# aufsatz_v2_3_usb.net
KiCad netlist of a schematic drawn in EAGLE
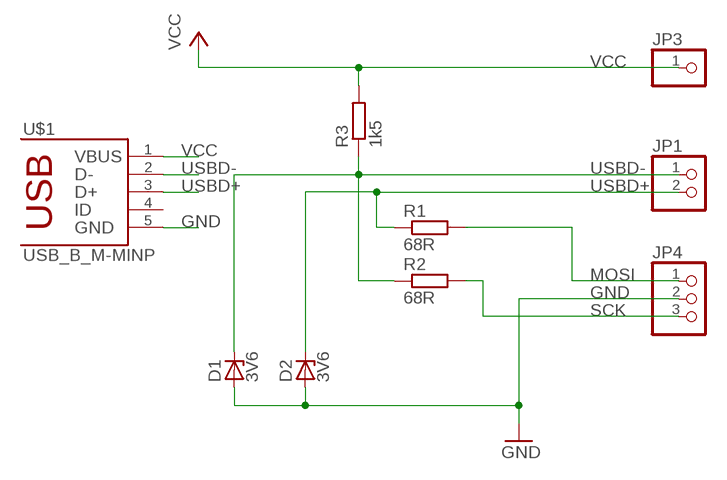
[diagram p0: schematic, sheet 1]

(export (version "E")
  (design (tool "Eeschema 10.0.6"))
  (components
    (comp (ref "D1")
      (value "3V6")
      (footprint "eagle-import:SOD80C")
      (libsource (lib "eagle-import") (part "ZENER-DIODESOD80C"))
    )
    (comp (ref "D2")
      (value "3V6")
      (footprint "eagle-import:SOD80C")
      (libsource (lib "eagle-import") (part "ZENER-DIODESOD80C"))
    )
    (comp (ref "JP1")
      (value "PINHD-1X2")
      (footprint "eagle-import:1X02")
      (libsource (lib "eagle-import") (part "PINHD-1X2"))
    )
    (comp (ref "JP3")
      (value "PINHD-1X1")
      (footprint "eagle-import:1X01")
      (libsource (lib "eagle-import") (part "PINHD-1X1"))
    )
    (comp (ref "JP4")
      (value "PINHD-1X3")
      (footprint "eagle-import:1X03")
      (libsource (lib "eagle-import") (part "PINHD-1X3"))
    )
    (comp (ref "R1")
      (value "68R")
      (footprint "eagle-import:R0805")
      (libsource (lib "eagle-import") (part "R-EU_R0805"))
    )
    (comp (ref "R2")
      (value "68R")
      (footprint "eagle-import:R0805")
      (libsource (lib "eagle-import") (part "R-EU_R0805"))
    )
    (comp (ref "R3")
      (value "1k5")
      (footprint "eagle-import:R0805")
      (libsource (lib "eagle-import") (part "R-EU_R0805"))
    )
    (comp (ref "U$1")
      (value "USB_B_M-MINP")
      (footprint "eagle-import:USB_B_MINI-PRINT")
      (libsource (lib "eagle-import") (part "USB_B_M-MINP"))
    )
  )
  (nets
    (net (code "1") (name "/MOSI") (class "Default")
      (node (ref "JP4") (pin "1") (pinfunction "1_1") (pintype "passive"))
      (node (ref "R1") (pin "2") (pinfunction "2_2") (pintype "passive"))
    )
    (net (code "2") (name "/SCK") (class "Default")
      (node (ref "JP4") (pin "3") (pinfunction "3_3") (pintype "passive"))
      (node (ref "R2") (pin "2") (pinfunction "2_2") (pintype "passive"))
    )
    (net (code "3") (name "/USBD+") (class "Default")
      (node (ref "D2") (pin "C") (pinfunction "C_C") (pintype "passive"))
      (node (ref "JP1") (pin "2") (pinfunction "2_2") (pintype "passive"))
      (node (ref "R1") (pin "1") (pinfunction "1_1") (pintype "passive"))
      (node (ref "U$1") (pin "3") (pinfunction "3_3") (pintype "passive"))
    )
    (net (code "4") (name "/USBD-") (class "Default")
      (node (ref "D1") (pin "C") (pinfunction "C_C") (pintype "passive"))
      (node (ref "JP1") (pin "1") (pinfunction "1_1") (pintype "passive"))
      (node (ref "R2") (pin "1") (pinfunction "1_1") (pintype "passive"))
      (node (ref "R3") (pin "1") (pinfunction "1_1") (pintype "passive"))
      (node (ref "U$1") (pin "2") (pinfunction "2_2") (pintype "passive"))
    )
    (net (code "5") (name "GND") (class "Default")
      (node (ref "D1") (pin "A") (pinfunction "A_A") (pintype "passive"))
      (node (ref "D2") (pin "A") (pinfunction "A_A") (pintype "passive"))
      (node (ref "JP4") (pin "2") (pinfunction "2_2") (pintype "passive"))
      (node (ref "U$1") (pin "5") (pinfunction "5_5") (pintype "passive"))
    )
    (net (code "6") (name "VCC") (class "Default")
      (node (ref "JP3") (pin "1") (pinfunction "1_1") (pintype "passive"))
      (node (ref "R3") (pin "2") (pinfunction "2_2") (pintype "passive"))
      (node (ref "U$1") (pin "1") (pinfunction "1_1") (pintype "passive"))
    )
    (net (code "7") (name "unconnected-(U$1-Pad4)") (class "Default")
      (node (ref "U$1") (pin "4") (pinfunction "4_4") (pintype "passive"))
    )
  )
)
